# JOYSW.net
KiCad netlist of a schematic drawn in EAGLE
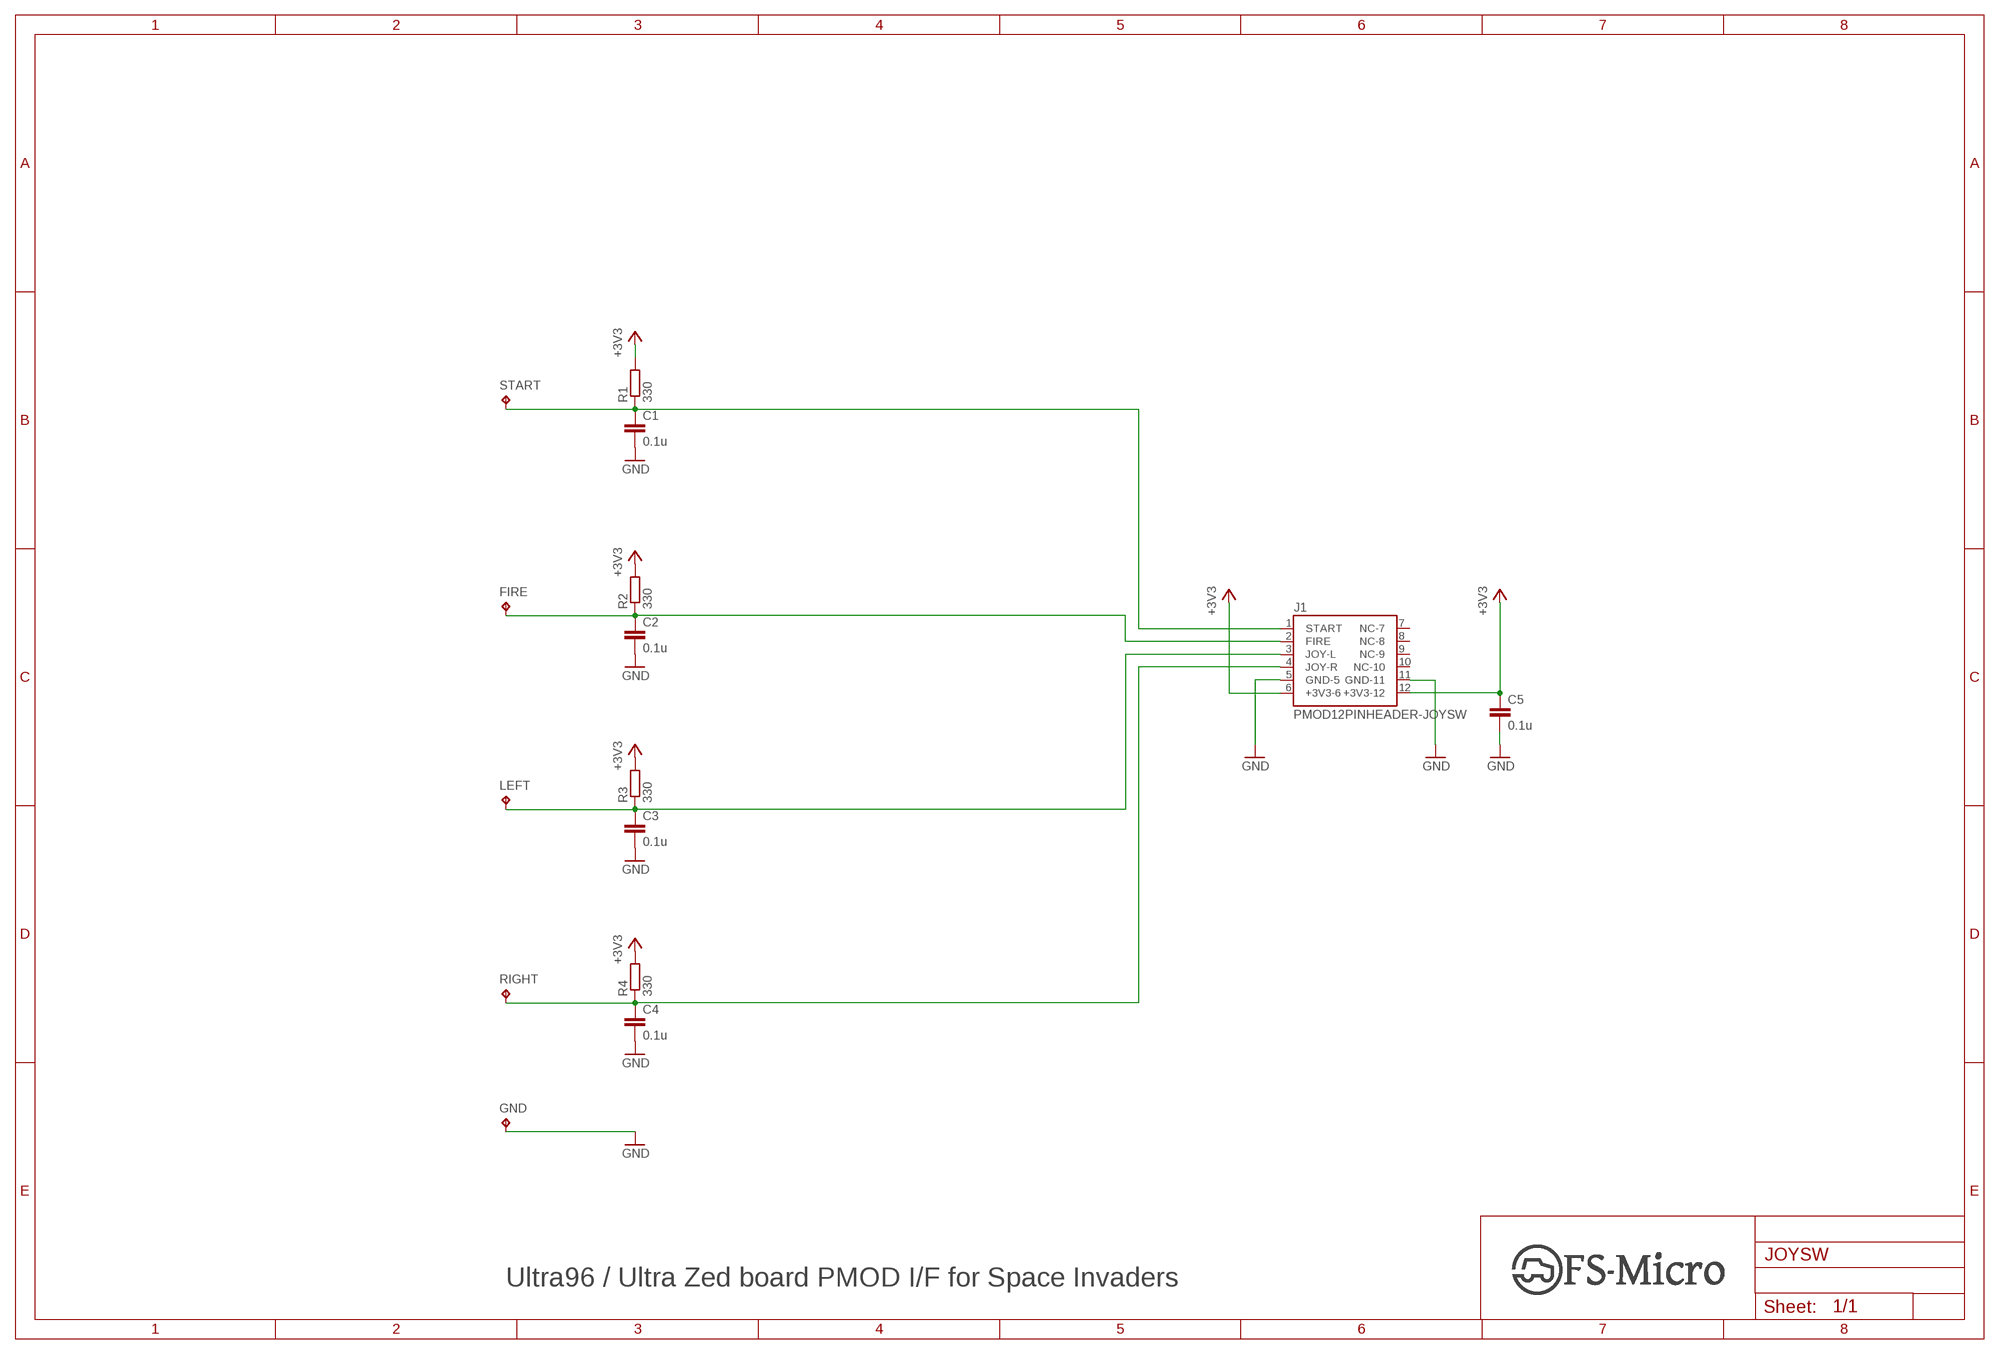
[diagram p0: schematic, sheet 1]

(export (version "E")
  (design (tool "Eeschema 10.0.6"))
  (components
    (comp (ref "C1")
      (value "0.1u")
      (footprint "eagle-import:C050-025X075")
      (libsource (lib "eagle-import") (part "C-EU050-025X075"))
    )
    (comp (ref "C2")
      (value "0.1u")
      (footprint "eagle-import:C050-025X075")
      (libsource (lib "eagle-import") (part "C-EU050-025X075"))
    )
    (comp (ref "C3")
      (value "0.1u")
      (footprint "eagle-import:C050-025X075")
      (libsource (lib "eagle-import") (part "C-EU050-025X075"))
    )
    (comp (ref "C4")
      (value "0.1u")
      (footprint "eagle-import:C050-025X075")
      (libsource (lib "eagle-import") (part "C-EU050-025X075"))
    )
    (comp (ref "C5")
      (value "0.1u")
      (footprint "eagle-import:C050-025X075")
      (libsource (lib "eagle-import") (part "C-EU050-025X075"))
    )
    (comp (ref "FIRE")
      (value "TPPAD1-13")
      (footprint "eagle-import:P1-13")
      (libsource (lib "eagle-import") (part "TPPAD1-13"))
    )
    (comp (ref "GND")
      (value "TPPAD1-13")
      (footprint "eagle-import:P1-13")
      (libsource (lib "eagle-import") (part "TPPAD1-13"))
    )
    (comp (ref "J1")
      (value "PMOD12PINHEADER-JOYSW")
      (footprint "eagle-import:PMOD12PINHEADER")
      (libsource (lib "eagle-import") (part "PMOD12PINHEADER-JOYSW"))
    )
    (comp (ref "LEFT")
      (value "TPPAD1-13")
      (footprint "eagle-import:P1-13")
      (libsource (lib "eagle-import") (part "TPPAD1-13"))
    )
    (comp (ref "R1")
      (value "330")
      (footprint "eagle-import:0207_7")
      (libsource (lib "eagle-import") (part "R-EU_0207/7"))
    )
    (comp (ref "R2")
      (value "330")
      (footprint "eagle-import:0207_7")
      (libsource (lib "eagle-import") (part "R-EU_0207/7"))
    )
    (comp (ref "R3")
      (value "330")
      (footprint "eagle-import:0207_7")
      (libsource (lib "eagle-import") (part "R-EU_0207/7"))
    )
    (comp (ref "R4")
      (value "330")
      (footprint "eagle-import:0207_7")
      (libsource (lib "eagle-import") (part "R-EU_0207/7"))
    )
    (comp (ref "RIGHT")
      (value "TPPAD1-13")
      (footprint "eagle-import:P1-13")
      (libsource (lib "eagle-import") (part "TPPAD1-13"))
    )
    (comp (ref "START")
      (value "TPPAD1-13")
      (footprint "eagle-import:P1-13")
      (libsource (lib "eagle-import") (part "TPPAD1-13"))
    )
  )
  (nets
    (net (code "1") (name "+3V3") (class "Default")
      (node (ref "C5") (pin "1") (pinfunction "1_1") (pintype "passive"))
      (node (ref "J1") (pin "12") (pinfunction "+3V3-12_12") (pintype "passive"))
      (node (ref "J1") (pin "6") (pinfunction "+3V3-6_6") (pintype "passive"))
      (node (ref "R1") (pin "2") (pinfunction "2_2") (pintype "passive"))
      (node (ref "R2") (pin "2") (pinfunction "2_2") (pintype "passive"))
      (node (ref "R3") (pin "2") (pinfunction "2_2") (pintype "passive"))
      (node (ref "R4") (pin "2") (pinfunction "2_2") (pintype "passive"))
    )
    (net (code "2") (name "GND") (class "Default")
      (node (ref "C1") (pin "2") (pinfunction "2_2") (pintype "passive"))
      (node (ref "C2") (pin "2") (pinfunction "2_2") (pintype "passive"))
      (node (ref "C3") (pin "2") (pinfunction "2_2") (pintype "passive"))
      (node (ref "C4") (pin "2") (pinfunction "2_2") (pintype "passive"))
      (node (ref "C5") (pin "2") (pinfunction "2_2") (pintype "passive"))
      (node (ref "GND") (pin "TP") (pinfunction "TP_TP") (pintype "input"))
      (node (ref "J1") (pin "11") (pinfunction "GND-11_11") (pintype "passive"))
      (node (ref "J1") (pin "5") (pinfunction "GND-5_5") (pintype "passive"))
    )
    (net (code "3") (name "Net-(J1-FIRE)") (class "Default")
      (node (ref "C2") (pin "1") (pinfunction "1_1") (pintype "passive"))
      (node (ref "FIRE") (pin "TP") (pinfunction "TP_TP") (pintype "input"))
      (node (ref "J1") (pin "2") (pinfunction "FIRE_2") (pintype "bidirectional"))
      (node (ref "R2") (pin "1") (pinfunction "1_1") (pintype "passive"))
    )
    (net (code "4") (name "Net-(J1-JOY-L)") (class "Default")
      (node (ref "C3") (pin "1") (pinfunction "1_1") (pintype "passive"))
      (node (ref "J1") (pin "3") (pinfunction "JOY-L_3") (pintype "bidirectional"))
      (node (ref "LEFT") (pin "TP") (pinfunction "TP_TP") (pintype "input"))
      (node (ref "R3") (pin "1") (pinfunction "1_1") (pintype "passive"))
    )
    (net (code "5") (name "Net-(J1-JOY-R)") (class "Default")
      (node (ref "C4") (pin "1") (pinfunction "1_1") (pintype "passive"))
      (node (ref "J1") (pin "4") (pinfunction "JOY-R_4") (pintype "bidirectional"))
      (node (ref "R4") (pin "1") (pinfunction "1_1") (pintype "passive"))
      (node (ref "RIGHT") (pin "TP") (pinfunction "TP_TP") (pintype "input"))
    )
    (net (code "6") (name "Net-(J1-START)") (class "Default")
      (node (ref "C1") (pin "1") (pinfunction "1_1") (pintype "passive"))
      (node (ref "J1") (pin "1") (pinfunction "START_1") (pintype "bidirectional"))
      (node (ref "R1") (pin "1") (pinfunction "1_1") (pintype "passive"))
      (node (ref "START") (pin "TP") (pinfunction "TP_TP") (pintype "input"))
    )
    (net (code "7") (name "unconnected-(J1-NC-7-Pad7)") (class "Default")
      (node (ref "J1") (pin "7") (pinfunction "NC-7_7") (pintype "no_connect"))
    )
    (net (code "8") (name "unconnected-(J1-NC-8-Pad8)") (class "Default")
      (node (ref "J1") (pin "8") (pinfunction "NC-8_8") (pintype "no_connect"))
    )
    (net (code "9") (name "unconnected-(J1-NC-9-Pad9)") (class "Default")
      (node (ref "J1") (pin "9") (pinfunction "NC-9_9") (pintype "no_connect"))
    )
    (net (code "10") (name "unconnected-(J1-NC-10-Pad10)") (class "Default")
      (node (ref "J1") (pin "10") (pinfunction "NC-10_10") (pintype "no_connect"))
    )
  )
)
